# EMSBoard.net
KiCad netlist of a schematic drawn in EAGLE
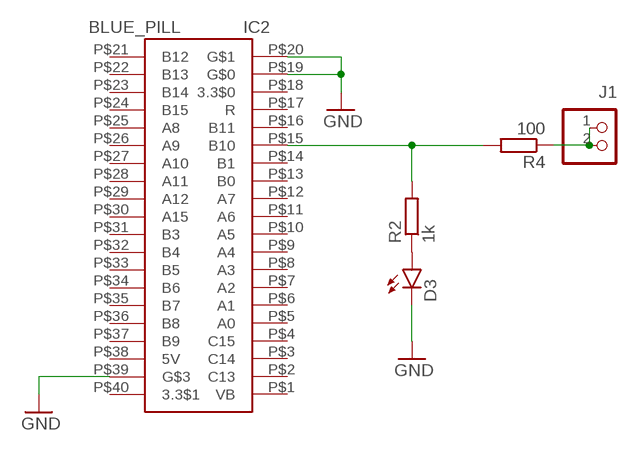
[diagram p0: schematic, sheet 1]

(export (version "E")
  (design (tool "Eeschema 10.0.6"))
  (components
    (comp (ref "D3")
      (value "LEDCHIP-LED0805")
      (footprint "eagle-import:CHIP-LED0805")
      (libsource (lib "eagle-import") (part "LEDCHIP-LED0805"))
    )
    (comp (ref "IC2")
      (value "BLUE_PILL")
      (footprint "eagle-import:BLUE_PILL")
      (libsource (lib "eagle-import") (part "BLUE_PILL"))
    )
    (comp (ref "J1")
      (value "S2B-XH-A")
      (footprint "eagle-import:S2B-XH-A")
      (libsource (lib "eagle-import") (part "S2B-XH-A"))
    )
    (comp (ref "R2")
      (value "1k")
      (footprint "eagle-import:R0603")
      (libsource (lib "eagle-import") (part "R-EU_R0603"))
    )
    (comp (ref "R4")
      (value "100")
      (footprint "eagle-import:R0603")
      (libsource (lib "eagle-import") (part "R-EU_R0603"))
    )
  )
  (nets
    (net (code "1") (name "GND") (class "Default")
      (node (ref "D3") (pin "C") (pinfunction "C_C") (pintype "passive"))
      (node (ref "IC2") (pin "P$19") (pinfunction "G$0_P$19") (pintype "passive"))
      (node (ref "IC2") (pin "P$20") (pinfunction "G$1_P$20") (pintype "passive"))
      (node (ref "IC2") (pin "P$39") (pinfunction "G$3_P$39") (pintype "passive"))
    )
    (net (code "2") (name "Net-(D3-PadA)") (class "Default")
      (node (ref "D3") (pin "A") (pinfunction "A_A") (pintype "passive"))
      (node (ref "R2") (pin "1") (pinfunction "1_1") (pintype "passive"))
    )
    (net (code "3") (name "Net-(IC2-B10)") (class "Default")
      (node (ref "IC2") (pin "P$15") (pinfunction "B10_P$15") (pintype "bidirectional"))
      (node (ref "R2") (pin "2") (pinfunction "2_2") (pintype "passive"))
      (node (ref "R4") (pin "2") (pinfunction "2_2") (pintype "passive"))
    )
    (net (code "4") (name "Net-(J1-Pad1)") (class "Default")
      (node (ref "J1") (pin "1") (pinfunction "1_1") (pintype "passive"))
      (node (ref "J1") (pin "2") (pinfunction "2_2") (pintype "passive"))
      (node (ref "R4") (pin "1") (pinfunction "1_1") (pintype "passive"))
    )
    (net (code "5") (name "unconnected-(IC2-3.3$0-PadP$18)") (class "Default")
      (node (ref "IC2") (pin "P$18") (pinfunction "3.3$0_P$18") (pintype "passive"))
    )
    (net (code "6") (name "unconnected-(IC2-3.3$1-PadP$40)") (class "Default")
      (node (ref "IC2") (pin "P$40") (pinfunction "3.3$1_P$40") (pintype "passive"))
    )
    (net (code "7") (name "unconnected-(IC2-5V-PadP$38)") (class "Default")
      (node (ref "IC2") (pin "P$38") (pinfunction "5V_P$38") (pintype "bidirectional"))
    )
    (net (code "8") (name "unconnected-(IC2-A0-PadP$5)") (class "Default")
      (node (ref "IC2") (pin "P$5") (pinfunction "A0_P$5") (pintype "bidirectional"))
    )
    (net (code "9") (name "unconnected-(IC2-A1-PadP$6)") (class "Default")
      (node (ref "IC2") (pin "P$6") (pinfunction "A1_P$6") (pintype "bidirectional"))
    )
    (net (code "10") (name "unconnected-(IC2-A2-PadP$7)") (class "Default")
      (node (ref "IC2") (pin "P$7") (pinfunction "A2_P$7") (pintype "bidirectional"))
    )
    (net (code "11") (name "unconnected-(IC2-A3-PadP$8)") (class "Default")
      (node (ref "IC2") (pin "P$8") (pinfunction "A3_P$8") (pintype "bidirectional"))
    )
    (net (code "12") (name "unconnected-(IC2-A4-PadP$9)") (class "Default")
      (node (ref "IC2") (pin "P$9") (pinfunction "A4_P$9") (pintype "bidirectional"))
    )
    (net (code "13") (name "unconnected-(IC2-A5-PadP$10)") (class "Default")
      (node (ref "IC2") (pin "P$10") (pinfunction "A5_P$10") (pintype "bidirectional"))
    )
    (net (code "14") (name "unconnected-(IC2-A6-PadP$11)") (class "Default")
      (node (ref "IC2") (pin "P$11") (pinfunction "A6_P$11") (pintype "bidirectional"))
    )
    (net (code "15") (name "unconnected-(IC2-A7-PadP$12)") (class "Default")
      (node (ref "IC2") (pin "P$12") (pinfunction "A7_P$12") (pintype "bidirectional"))
    )
    (net (code "16") (name "unconnected-(IC2-A8-PadP$25)") (class "Default")
      (node (ref "IC2") (pin "P$25") (pinfunction "A8_P$25") (pintype "bidirectional"))
    )
    (net (code "17") (name "unconnected-(IC2-A9-PadP$26)") (class "Default")
      (node (ref "IC2") (pin "P$26") (pinfunction "A9_P$26") (pintype "bidirectional"))
    )
    (net (code "18") (name "unconnected-(IC2-A10-PadP$27)") (class "Default")
      (node (ref "IC2") (pin "P$27") (pinfunction "A10_P$27") (pintype "bidirectional"))
    )
    (net (code "19") (name "unconnected-(IC2-A11-PadP$28)") (class "Default")
      (node (ref "IC2") (pin "P$28") (pinfunction "A11_P$28") (pintype "bidirectional"))
    )
    (net (code "20") (name "unconnected-(IC2-A12-PadP$29)") (class "Default")
      (node (ref "IC2") (pin "P$29") (pinfunction "A12_P$29") (pintype "bidirectional"))
    )
    (net (code "21") (name "unconnected-(IC2-A15-PadP$30)") (class "Default")
      (node (ref "IC2") (pin "P$30") (pinfunction "A15_P$30") (pintype "bidirectional"))
    )
    (net (code "22") (name "unconnected-(IC2-B0-PadP$13)") (class "Default")
      (node (ref "IC2") (pin "P$13") (pinfunction "B0_P$13") (pintype "bidirectional"))
    )
    (net (code "23") (name "unconnected-(IC2-B1-PadP$14)") (class "Default")
      (node (ref "IC2") (pin "P$14") (pinfunction "B1_P$14") (pintype "bidirectional"))
    )
    (net (code "24") (name "unconnected-(IC2-B3-PadP$31)") (class "Default")
      (node (ref "IC2") (pin "P$31") (pinfunction "B3_P$31") (pintype "bidirectional"))
    )
    (net (code "25") (name "unconnected-(IC2-B4-PadP$32)") (class "Default")
      (node (ref "IC2") (pin "P$32") (pinfunction "B4_P$32") (pintype "bidirectional"))
    )
    (net (code "26") (name "unconnected-(IC2-B5-PadP$33)") (class "Default")
      (node (ref "IC2") (pin "P$33") (pinfunction "B5_P$33") (pintype "bidirectional"))
    )
    (net (code "27") (name "unconnected-(IC2-B6-PadP$34)") (class "Default")
      (node (ref "IC2") (pin "P$34") (pinfunction "B6_P$34") (pintype "bidirectional"))
    )
    (net (code "28") (name "unconnected-(IC2-B7-PadP$35)") (class "Default")
      (node (ref "IC2") (pin "P$35") (pinfunction "B7_P$35") (pintype "bidirectional"))
    )
    (net (code "29") (name "unconnected-(IC2-B8-PadP$36)") (class "Default")
      (node (ref "IC2") (pin "P$36") (pinfunction "B8_P$36") (pintype "bidirectional"))
    )
    (net (code "30") (name "unconnected-(IC2-B9-PadP$37)") (class "Default")
      (node (ref "IC2") (pin "P$37") (pinfunction "B9_P$37") (pintype "bidirectional"))
    )
    (net (code "31") (name "unconnected-(IC2-B11-PadP$16)") (class "Default")
      (node (ref "IC2") (pin "P$16") (pinfunction "B11_P$16") (pintype "bidirectional"))
    )
    (net (code "32") (name "unconnected-(IC2-B12-PadP$21)") (class "Default")
      (node (ref "IC2") (pin "P$21") (pinfunction "B12_P$21") (pintype "bidirectional"))
    )
    (net (code "33") (name "unconnected-(IC2-B13-PadP$22)") (class "Default")
      (node (ref "IC2") (pin "P$22") (pinfunction "B13_P$22") (pintype "bidirectional"))
    )
    (net (code "34") (name "unconnected-(IC2-B14-PadP$23)") (class "Default")
      (node (ref "IC2") (pin "P$23") (pinfunction "B14_P$23") (pintype "bidirectional"))
    )
    (net (code "35") (name "unconnected-(IC2-B15-PadP$24)") (class "Default")
      (node (ref "IC2") (pin "P$24") (pinfunction "B15_P$24") (pintype "bidirectional"))
    )
    (net (code "36") (name "unconnected-(IC2-C13-PadP$2)") (class "Default")
      (node (ref "IC2") (pin "P$2") (pinfunction "C13_P$2") (pintype "bidirectional"))
    )
    (net (code "37") (name "unconnected-(IC2-C14-PadP$3)") (class "Default")
      (node (ref "IC2") (pin "P$3") (pinfunction "C14_P$3") (pintype "bidirectional"))
    )
    (net (code "38") (name "unconnected-(IC2-C15-PadP$4)") (class "Default")
      (node (ref "IC2") (pin "P$4") (pinfunction "C15_P$4") (pintype "bidirectional"))
    )
    (net (code "39") (name "unconnected-(IC2-R-PadP$17)") (class "Default")
      (node (ref "IC2") (pin "P$17") (pinfunction "R_P$17") (pintype "bidirectional"))
    )
    (net (code "40") (name "unconnected-(IC2-VB-PadP$1)") (class "Default")
      (node (ref "IC2") (pin "P$1") (pinfunction "VB_P$1") (pintype "bidirectional"))
    )
  )
)
